# m4_Dev_Board.net
KiCad netlist of a schematic drawn in EAGLE
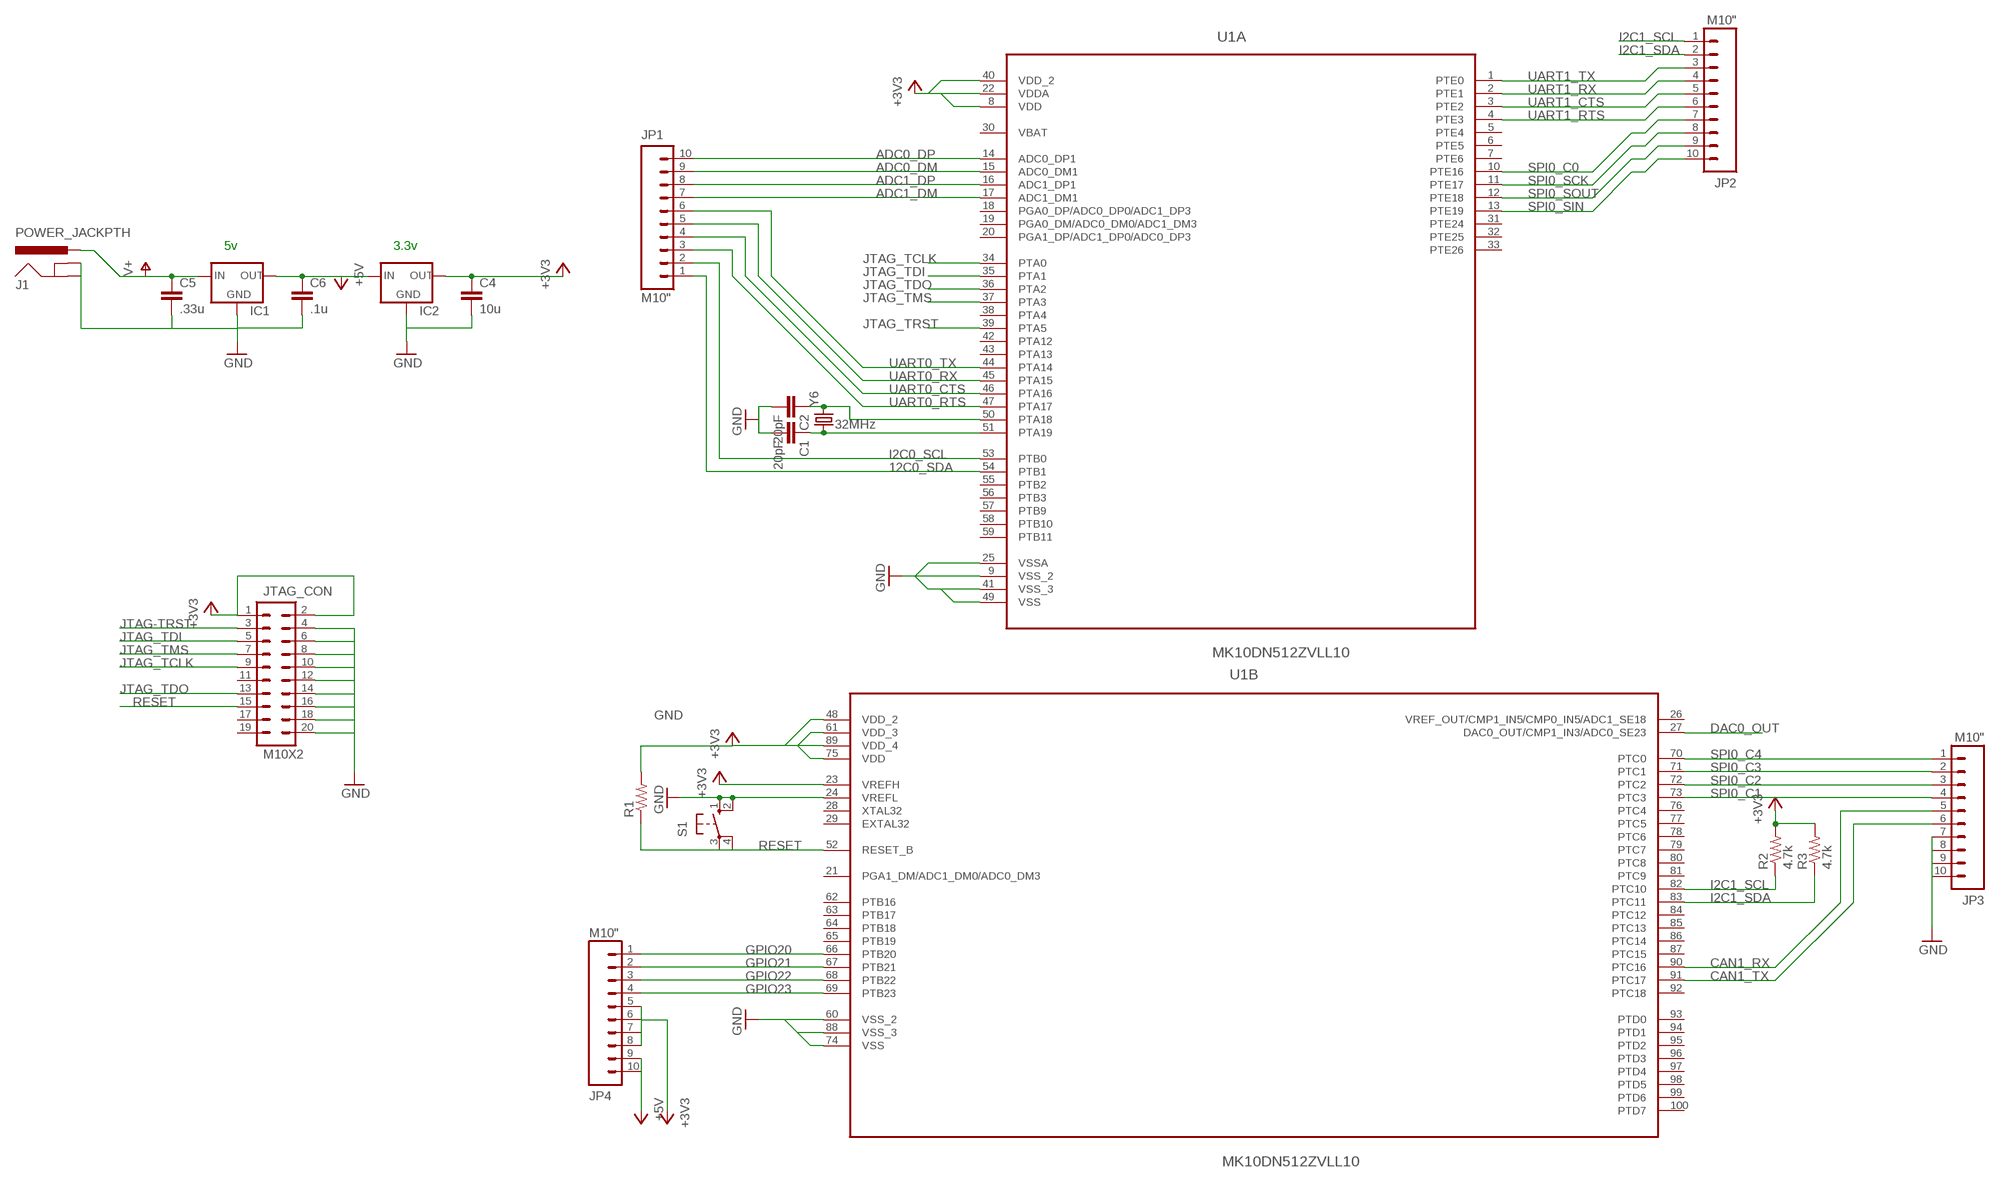
[diagram p0: schematic, sheet 1]

(export (version "E")
  (design (tool "Eeschema 10.0.6"))
  (components
    (comp (ref "C1")
      (value "20pF")
      (footprint "eagle-import:CAP-PTH-5MM")
      (libsource (lib "eagle-import") (part "CAPPTH1"))
    )
    (comp (ref "C2")
      (value "20pF")
      (footprint "eagle-import:CAP-PTH-5MM")
      (libsource (lib "eagle-import") (part "CAPPTH1"))
    )
    (comp (ref "C4")
      (value "10u")
      (footprint "eagle-import:CAP-PTH-5MM")
      (libsource (lib "eagle-import") (part "CAPPTH1"))
    )
    (comp (ref "C5")
      (value ".33u")
      (footprint "eagle-import:CAP-PTH-5MM")
      (libsource (lib "eagle-import") (part "CAPPTH1"))
    )
    (comp (ref "C6")
      (value ".1u")
      (footprint "eagle-import:CAP-PTH-5MM")
      (libsource (lib "eagle-import") (part "CAPPTH1"))
    )
    (comp (ref "IC1")
      (value "V_REG_78XXSINK")
      (footprint "eagle-import:TO220-IGO")
      (libsource (lib "eagle-import") (part "V_REG_78XXSINK"))
    )
    (comp (ref "IC2")
      (value "V_REG_78XXSINK")
      (footprint "eagle-import:TO220-IGO")
      (libsource (lib "eagle-import") (part "V_REG_78XXSINK"))
    )
    (comp (ref "J1")
      (value "POWER_JACKPTH")
      (footprint "eagle-import:POWER_JACK_PTH")
      (libsource (lib "eagle-import") (part "POWER_JACKPTH"))
    )
    (comp (ref "JP1")
      (value "M10\"")
      (footprint "eagle-import:1X10")
      (libsource (lib "eagle-import") (part "M10{dblquote}"))
    )
    (comp (ref "JP2")
      (value "M10\"")
      (footprint "eagle-import:1X10")
      (libsource (lib "eagle-import") (part "M10{dblquote}"))
    )
    (comp (ref "JP3")
      (value "M10\"")
      (footprint "eagle-import:1X10")
      (libsource (lib "eagle-import") (part "M10{dblquote}"))
    )
    (comp (ref "JP4")
      (value "M10\"")
      (footprint "eagle-import:1X10")
      (libsource (lib "eagle-import") (part "M10{dblquote}"))
    )
    (comp (ref "JTAG_CON")
      (value "M10X2")
      (footprint "eagle-import:2X10")
      (libsource (lib "eagle-import") (part "M10X2"))
    )
    (comp (ref "R1")
      (value "RESISTORPTH-1/4W")
      (footprint "eagle-import:AXIAL-0.4")
      (libsource (lib "eagle-import") (part "RESISTORPTH-1/4W"))
    )
    (comp (ref "R2")
      (value "4.7k")
      (footprint "eagle-import:AXIAL-0.4")
      (libsource (lib "eagle-import") (part "RESISTORPTH-1/4W"))
    )
    (comp (ref "R3")
      (value "4.7k")
      (footprint "eagle-import:AXIAL-0.4")
      (libsource (lib "eagle-import") (part "RESISTORPTH-1/4W"))
    )
    (comp (ref "S1")
      (value "10-XX")
      (footprint "eagle-import:B3F-10XX")
      (fields (field (name "MPN") "B3F-1000"))
      (libsource (lib "eagle-import") (part "10-XX"))
    )
    (comp (ref "U1")
      (value "MK10DN512ZVLL10")
      (footprint "eagle-import:QFP50P1600X1600X170-100N")
      (libsource (lib "eagle-import") (part "MK10DN512ZVLL10"))
    )
    (comp (ref "Y6")
      (value "32MHz")
      (footprint "eagle-import:CRYSTAL-SMD-5X3")
      (libsource (lib "eagle-import") (part "CRYSTAL5X3"))
    )
  )
  (nets
    (net (code "1") (name "+3V3") (class "Default")
      (node (ref "C4") (pin "1") (pinfunction "1_1") (pintype "passive"))
      (node (ref "IC2") (pin "OUT") (pinfunction "OUT_OUT") (pintype "output"))
      (node (ref "JP4") (pin "5") (pinfunction "5_5") (pintype "passive"))
      (node (ref "JP4") (pin "6") (pinfunction "6_6") (pintype "passive"))
      (node (ref "JP4") (pin "7") (pinfunction "7_7") (pintype "passive"))
      (node (ref "JP4") (pin "8") (pinfunction "8_8") (pintype "passive"))
      (node (ref "JTAG_CON") (pin "1") (pinfunction "1_1") (pintype "passive"))
      (node (ref "JTAG_CON") (pin "2") (pinfunction "2_2") (pintype "passive"))
      (node (ref "R1") (pin "P$2") (pinfunction "2_P$2") (pintype "passive"))
      (node (ref "R2") (pin "P$2") (pinfunction "2_P$2") (pintype "passive"))
      (node (ref "R3") (pin "P$2") (pinfunction "2_P$2") (pintype "passive"))
      (node (ref "U1") (pin "22") (pinfunction "VDDA_22") (pintype "power_in"))
      (node (ref "U1") (pin "23") (pinfunction "VREFH_23") (pintype "passive"))
      (node (ref "U1") (pin "40") (pinfunction "VDD_2_40") (pintype "power_in"))
      (node (ref "U1") (pin "48") (pinfunction "VDD_2_48") (pintype "power_in"))
      (node (ref "U1") (pin "61") (pinfunction "VDD_3_61") (pintype "power_in"))
      (node (ref "U1") (pin "75") (pinfunction "VDD_75") (pintype "power_in"))
      (node (ref "U1") (pin "8") (pinfunction "VDD_8") (pintype "power_in"))
      (node (ref "U1") (pin "89") (pinfunction "VDD_4_89") (pintype "power_in"))
    )
    (net (code "2") (name "+5V") (class "Default")
      (node (ref "C6") (pin "1") (pinfunction "1_1") (pintype "passive"))
      (node (ref "IC1") (pin "OUT") (pinfunction "OUT_OUT") (pintype "output"))
      (node (ref "IC2") (pin "IN") (pinfunction "IN_IN") (pintype "input"))
      (node (ref "JP4") (pin "10") (pinfunction "10_10") (pintype "passive"))
      (node (ref "JP4") (pin "9") (pinfunction "9_9") (pintype "passive"))
    )
    (net (code "3") (name "/12C0_SDA") (class "Default")
      (node (ref "JP1") (pin "1") (pinfunction "1_1") (pintype "passive"))
      (node (ref "U1") (pin "54") (pinfunction "PTB1_54") (pintype "bidirectional"))
    )
    (net (code "4") (name "/ADC0_DM") (class "Default")
      (node (ref "JP1") (pin "9") (pinfunction "9_9") (pintype "passive"))
      (node (ref "U1") (pin "15") (pinfunction "ADC0_DM1_15") (pintype "passive"))
    )
    (net (code "5") (name "/ADC0_DP") (class "Default")
      (node (ref "JP1") (pin "10") (pinfunction "10_10") (pintype "passive"))
      (node (ref "U1") (pin "14") (pinfunction "ADC0_DP1_14") (pintype "passive"))
    )
    (net (code "6") (name "/ADC1_DM") (class "Default")
      (node (ref "JP1") (pin "7") (pinfunction "7_7") (pintype "passive"))
      (node (ref "U1") (pin "17") (pinfunction "ADC1_DM1_17") (pintype "passive"))
    )
    (net (code "7") (name "/ADC1_DP") (class "Default")
      (node (ref "JP1") (pin "8") (pinfunction "8_8") (pintype "passive"))
      (node (ref "U1") (pin "16") (pinfunction "ADC1_DP1_16") (pintype "passive"))
    )
    (net (code "8") (name "/CAN1_RX") (class "Default")
      (node (ref "JP3") (pin "5") (pinfunction "5_5") (pintype "passive"))
      (node (ref "U1") (pin "90") (pinfunction "PTC16_90") (pintype "bidirectional"))
    )
    (net (code "9") (name "/CAN1_TX") (class "Default")
      (node (ref "JP3") (pin "6") (pinfunction "6_6") (pintype "passive"))
      (node (ref "U1") (pin "91") (pinfunction "PTC17_91") (pintype "bidirectional"))
    )
    (net (code "10") (name "/DAC0_OUT") (class "Default")
      (node (ref "U1") (pin "27") (pinfunction "DAC0_OUT/CMP1_IN3/ADC0_SE23_27") (pintype "passive"))
    )
    (net (code "11") (name "/GPIO20") (class "Default")
      (node (ref "JP4") (pin "1") (pinfunction "1_1") (pintype "passive"))
      (node (ref "U1") (pin "66") (pinfunction "PTB20_66") (pintype "bidirectional"))
    )
    (net (code "12") (name "/GPIO21") (class "Default")
      (node (ref "JP4") (pin "2") (pinfunction "2_2") (pintype "passive"))
      (node (ref "U1") (pin "67") (pinfunction "PTB21_67") (pintype "bidirectional"))
    )
    (net (code "13") (name "/GPIO22") (class "Default")
      (node (ref "JP4") (pin "3") (pinfunction "3_3") (pintype "passive"))
      (node (ref "U1") (pin "68") (pinfunction "PTB22_68") (pintype "bidirectional"))
    )
    (net (code "14") (name "/GPIO23") (class "Default")
      (node (ref "JP4") (pin "4") (pinfunction "4_4") (pintype "passive"))
      (node (ref "U1") (pin "69") (pinfunction "PTB23_69") (pintype "bidirectional"))
    )
    (net (code "15") (name "/I2C0_SCL") (class "Default")
      (node (ref "JP1") (pin "2") (pinfunction "2_2") (pintype "passive"))
      (node (ref "U1") (pin "53") (pinfunction "PTB0_53") (pintype "bidirectional"))
    )
    (net (code "16") (name "/I2C1_SCL") (class "Default")
      (node (ref "JP2") (pin "1") (pinfunction "1_1") (pintype "passive"))
      (node (ref "R2") (pin "P$1") (pinfunction "1_P$1") (pintype "passive"))
      (node (ref "U1") (pin "82") (pinfunction "PTC10_82") (pintype "bidirectional"))
    )
    (net (code "17") (name "/I2C1_SDA") (class "Default")
      (node (ref "JP2") (pin "2") (pinfunction "2_2") (pintype "passive"))
      (node (ref "R3") (pin "P$1") (pinfunction "1_P$1") (pintype "passive"))
      (node (ref "U1") (pin "83") (pinfunction "PTC11_83") (pintype "bidirectional"))
    )
    (net (code "18") (name "/JTAG-TRST") (class "Default")
      (node (ref "JTAG_CON") (pin "3") (pinfunction "3_3") (pintype "passive"))
    )
    (net (code "19") (name "/JTAG_TCLK") (class "Default")
      (node (ref "JTAG_CON") (pin "9") (pinfunction "9_9") (pintype "passive"))
      (node (ref "U1") (pin "34") (pinfunction "PTA0_34") (pintype "bidirectional"))
    )
    (net (code "20") (name "/JTAG_TDI") (class "Default")
      (node (ref "JTAG_CON") (pin "5") (pinfunction "5_5") (pintype "passive"))
      (node (ref "U1") (pin "35") (pinfunction "PTA1_35") (pintype "bidirectional"))
    )
    (net (code "21") (name "/JTAG_TDO") (class "Default")
      (node (ref "JTAG_CON") (pin "13") (pinfunction "13_13") (pintype "passive"))
      (node (ref "U1") (pin "36") (pinfunction "PTA2_36") (pintype "bidirectional"))
    )
    (net (code "22") (name "/JTAG_TMS") (class "Default")
      (node (ref "JTAG_CON") (pin "7") (pinfunction "7_7") (pintype "passive"))
      (node (ref "U1") (pin "37") (pinfunction "PTA3_37") (pintype "bidirectional"))
    )
    (net (code "23") (name "/JTAG_TRST") (class "Default")
      (node (ref "U1") (pin "39") (pinfunction "PTA5_39") (pintype "bidirectional"))
    )
    (net (code "24") (name "/RESET") (class "Default")
      (node (ref "JTAG_CON") (pin "15") (pinfunction "15_15") (pintype "passive"))
      (node (ref "R1") (pin "P$1") (pinfunction "1_P$1") (pintype "passive"))
      (node (ref "S1") (pin "3") (pinfunction "P_3") (pintype "passive"))
      (node (ref "S1") (pin "4") (pinfunction "P1_4") (pintype "passive"))
      (node (ref "U1") (pin "52") (pinfunction "RESET_B_52") (pintype "passive"))
    )
    (net (code "25") (name "/SPI0_C0") (class "Default")
      (node (ref "JP2") (pin "7") (pinfunction "7_7") (pintype "passive"))
      (node (ref "U1") (pin "10") (pinfunction "PTE16_10") (pintype "bidirectional"))
    )
    (net (code "26") (name "/SPI0_C1") (class "Default")
      (node (ref "JP3") (pin "4") (pinfunction "4_4") (pintype "passive"))
      (node (ref "U1") (pin "73") (pinfunction "PTC3_73") (pintype "bidirectional"))
    )
    (net (code "27") (name "/SPI0_C2") (class "Default")
      (node (ref "JP3") (pin "3") (pinfunction "3_3") (pintype "passive"))
      (node (ref "U1") (pin "72") (pinfunction "PTC2_72") (pintype "bidirectional"))
    )
    (net (code "28") (name "/SPI0_C3") (class "Default")
      (node (ref "JP3") (pin "2") (pinfunction "2_2") (pintype "passive"))
      (node (ref "U1") (pin "71") (pinfunction "PTC1_71") (pintype "bidirectional"))
    )
    (net (code "29") (name "/SPI0_C4") (class "Default")
      (node (ref "JP3") (pin "1") (pinfunction "1_1") (pintype "passive"))
      (node (ref "U1") (pin "70") (pinfunction "PTC0_70") (pintype "bidirectional"))
    )
    (net (code "30") (name "/SPI0_SCK") (class "Default")
      (node (ref "JP2") (pin "8") (pinfunction "8_8") (pintype "passive"))
      (node (ref "U1") (pin "11") (pinfunction "PTE17_11") (pintype "bidirectional"))
    )
    (net (code "31") (name "/SPI0_SIN") (class "Default")
      (node (ref "JP2") (pin "10") (pinfunction "10_10") (pintype "passive"))
      (node (ref "U1") (pin "13") (pinfunction "PTE19_13") (pintype "bidirectional"))
    )
    (net (code "32") (name "/SPI0_SOUT") (class "Default")
      (node (ref "JP2") (pin "9") (pinfunction "9_9") (pintype "passive"))
      (node (ref "U1") (pin "12") (pinfunction "PTE18_12") (pintype "bidirectional"))
    )
    (net (code "33") (name "/UART0_CTS") (class "Default")
      (node (ref "JP1") (pin "4") (pinfunction "4_4") (pintype "passive"))
      (node (ref "U1") (pin "46") (pinfunction "PTA16_46") (pintype "bidirectional"))
    )
    (net (code "34") (name "/UART0_RTS") (class "Default")
      (node (ref "JP1") (pin "3") (pinfunction "3_3") (pintype "passive"))
      (node (ref "U1") (pin "47") (pinfunction "PTA17_47") (pintype "bidirectional"))
    )
    (net (code "35") (name "/UART0_RX") (class "Default")
      (node (ref "JP1") (pin "5") (pinfunction "5_5") (pintype "passive"))
      (node (ref "U1") (pin "45") (pinfunction "PTA15_45") (pintype "bidirectional"))
    )
    (net (code "36") (name "/UART0_TX") (class "Default")
      (node (ref "JP1") (pin "6") (pinfunction "6_6") (pintype "passive"))
      (node (ref "U1") (pin "44") (pinfunction "PTA14_44") (pintype "bidirectional"))
    )
    (net (code "37") (name "/UART1_CTS") (class "Default")
      (node (ref "JP2") (pin "5") (pinfunction "5_5") (pintype "passive"))
      (node (ref "U1") (pin "3") (pinfunction "PTE2_3") (pintype "bidirectional"))
    )
    (net (code "38") (name "/UART1_RTS") (class "Default")
      (node (ref "JP2") (pin "6") (pinfunction "6_6") (pintype "passive"))
      (node (ref "U1") (pin "4") (pinfunction "PTE3_4") (pintype "bidirectional"))
    )
    (net (code "39") (name "/UART1_RX") (class "Default")
      (node (ref "JP2") (pin "4") (pinfunction "4_4") (pintype "passive"))
      (node (ref "U1") (pin "2") (pinfunction "PTE1_2") (pintype "bidirectional"))
    )
    (net (code "40") (name "/UART1_TX") (class "Default")
      (node (ref "JP2") (pin "3") (pinfunction "3_3") (pintype "passive"))
      (node (ref "U1") (pin "1") (pinfunction "PTE0_1") (pintype "bidirectional"))
    )
    (net (code "41") (name "/VBAT") (class "Default")
      (node (ref "U1") (pin "30") (pinfunction "VBAT_30") (pintype "power_in"))
    )
    (net (code "42") (name "GND") (class "Default")
      (node (ref "C1") (pin "2") (pinfunction "2_2") (pintype "passive"))
      (node (ref "C2") (pin "2") (pinfunction "2_2") (pintype "passive"))
      (node (ref "C4") (pin "2") (pinfunction "2_2") (pintype "passive"))
      (node (ref "C5") (pin "2") (pinfunction "2_2") (pintype "passive"))
      (node (ref "C6") (pin "2") (pinfunction "2_2") (pintype "passive"))
      (node (ref "IC1") (pin "GND") (pinfunction "GND_GND") (pintype "input"))
      (node (ref "IC2") (pin "GND") (pinfunction "GND_GND") (pintype "input"))
      (node (ref "J1") (pin "GND") (pinfunction "GND_GND") (pintype "bidirectional"))
      (node (ref "J1") (pin "GNDBREAK") (pinfunction "GNDBREAK_GNDBREAK") (pintype "bidirectional"))
      (node (ref "JP3") (pin "10") (pinfunction "10_10") (pintype "passive"))
      (node (ref "JP3") (pin "7") (pinfunction "7_7") (pintype "passive"))
      (node (ref "JP3") (pin "8") (pinfunction "8_8") (pintype "passive"))
      (node (ref "JP3") (pin "9") (pinfunction "9_9") (pintype "passive"))
      (node (ref "JTAG_CON") (pin "10") (pinfunction "10_10") (pintype "passive"))
      (node (ref "JTAG_CON") (pin "12") (pinfunction "12_12") (pintype "passive"))
      (node (ref "JTAG_CON") (pin "14") (pinfunction "14_14") (pintype "passive"))
      (node (ref "JTAG_CON") (pin "16") (pinfunction "16_16") (pintype "passive"))
      (node (ref "JTAG_CON") (pin "18") (pinfunction "18_18") (pintype "passive"))
      (node (ref "JTAG_CON") (pin "20") (pinfunction "20_20") (pintype "passive"))
      (node (ref "JTAG_CON") (pin "4") (pinfunction "4_4") (pintype "passive"))
      (node (ref "JTAG_CON") (pin "6") (pinfunction "6_6") (pintype "passive"))
      (node (ref "JTAG_CON") (pin "8") (pinfunction "8_8") (pintype "passive"))
      (node (ref "S1") (pin "1") (pinfunction "S_1") (pintype "passive"))
      (node (ref "S1") (pin "2") (pinfunction "S1_2") (pintype "passive"))
      (node (ref "U1") (pin "24") (pinfunction "VREFL_24") (pintype "passive"))
      (node (ref "U1") (pin "25") (pinfunction "VSSA_25") (pintype "passive"))
      (node (ref "U1") (pin "41") (pinfunction "VSS_3_41") (pintype "passive"))
      (node (ref "U1") (pin "49") (pinfunction "VSS_49") (pintype "passive"))
      (node (ref "U1") (pin "60") (pinfunction "VSS_2_60") (pintype "passive"))
      (node (ref "U1") (pin "74") (pinfunction "VSS_74") (pintype "passive"))
      (node (ref "U1") (pin "88") (pinfunction "VSS_3_88") (pintype "passive"))
      (node (ref "U1") (pin "9") (pinfunction "VSS_2_9") (pintype "passive"))
    )
    (net (code "43") (name "Net-(U1A-PTA18)") (class "Default")
      (node (ref "C2") (pin "1") (pinfunction "1_1") (pintype "passive"))
      (node (ref "U1") (pin "50") (pinfunction "PTA18_50") (pintype "bidirectional"))
      (node (ref "Y6") (pin "3") (pinfunction "2_3") (pintype "passive"))
    )
    (net (code "44") (name "Net-(U1A-PTA19)") (class "Default")
      (node (ref "C1") (pin "1") (pinfunction "1_1") (pintype "passive"))
      (node (ref "U1") (pin "51") (pinfunction "PTA19_51") (pintype "bidirectional"))
      (node (ref "Y6") (pin "1") (pinfunction "1_1") (pintype "passive"))
    )
    (net (code "45") (name "V+") (class "Default")
      (node (ref "C5") (pin "1") (pinfunction "1_1") (pintype "passive"))
      (node (ref "IC1") (pin "IN") (pinfunction "IN_IN") (pintype "input"))
      (node (ref "J1") (pin "PWR") (pinfunction "PWR_PWR") (pintype "bidirectional"))
    )
    (net (code "46") (name "unconnected-(JTAG_CON-Pad11)") (class "Default")
      (node (ref "JTAG_CON") (pin "11") (pinfunction "11_11") (pintype "passive"))
    )
    (net (code "47") (name "unconnected-(JTAG_CON-Pad17)") (class "Default")
      (node (ref "JTAG_CON") (pin "17") (pinfunction "17_17") (pintype "passive"))
    )
    (net (code "48") (name "unconnected-(JTAG_CON-Pad19)") (class "Default")
      (node (ref "JTAG_CON") (pin "19") (pinfunction "19_19") (pintype "passive"))
    )
    (net (code "49") (name "unconnected-(U1A-PGA0_DM{slash}ADC0_DM0{slash}ADC1_DM3-Pad19)") (class "Default")
      (node (ref "U1") (pin "19") (pinfunction "PGA0_DM/ADC0_DM0/ADC1_DM3_19") (pintype "passive"))
    )
    (net (code "50") (name "unconnected-(U1A-PGA0_DP{slash}ADC0_DP0{slash}ADC1_DP3-Pad18)") (class "Default")
      (node (ref "U1") (pin "18") (pinfunction "PGA0_DP/ADC0_DP0/ADC1_DP3_18") (pintype "passive"))
    )
    (net (code "51") (name "unconnected-(U1A-PGA1_DP{slash}ADC1_DP0{slash}ADC0_DP3-Pad20)") (class "Default")
      (node (ref "U1") (pin "20") (pinfunction "PGA1_DP/ADC1_DP0/ADC0_DP3_20") (pintype "passive"))
    )
    (net (code "52") (name "unconnected-(U1A-PTA4-Pad38)") (class "Default")
      (node (ref "U1") (pin "38") (pinfunction "PTA4_38") (pintype "bidirectional"))
    )
    (net (code "53") (name "unconnected-(U1A-PTA12-Pad42)") (class "Default")
      (node (ref "U1") (pin "42") (pinfunction "PTA12_42") (pintype "bidirectional"))
    )
    (net (code "54") (name "unconnected-(U1A-PTA13-Pad43)") (class "Default")
      (node (ref "U1") (pin "43") (pinfunction "PTA13_43") (pintype "bidirectional"))
    )
    (net (code "55") (name "unconnected-(U1A-PTB2-Pad55)") (class "Default")
      (node (ref "U1") (pin "55") (pinfunction "PTB2_55") (pintype "bidirectional"))
    )
    (net (code "56") (name "unconnected-(U1A-PTB3-Pad56)") (class "Default")
      (node (ref "U1") (pin "56") (pinfunction "PTB3_56") (pintype "bidirectional"))
    )
    (net (code "57") (name "unconnected-(U1A-PTB9-Pad57)") (class "Default")
      (node (ref "U1") (pin "57") (pinfunction "PTB9_57") (pintype "bidirectional"))
    )
    (net (code "58") (name "unconnected-(U1A-PTB10-Pad58)") (class "Default")
      (node (ref "U1") (pin "58") (pinfunction "PTB10_58") (pintype "bidirectional"))
    )
    (net (code "59") (name "unconnected-(U1A-PTB11-Pad59)") (class "Default")
      (node (ref "U1") (pin "59") (pinfunction "PTB11_59") (pintype "bidirectional"))
    )
    (net (code "60") (name "unconnected-(U1A-PTE4-Pad5)") (class "Default")
      (node (ref "U1") (pin "5") (pinfunction "PTE4_5") (pintype "bidirectional"))
    )
    (net (code "61") (name "unconnected-(U1A-PTE5-Pad6)") (class "Default")
      (node (ref "U1") (pin "6") (pinfunction "PTE5_6") (pintype "bidirectional"))
    )
    (net (code "62") (name "unconnected-(U1A-PTE6-Pad7)") (class "Default")
      (node (ref "U1") (pin "7") (pinfunction "PTE6_7") (pintype "bidirectional"))
    )
    (net (code "63") (name "unconnected-(U1A-PTE24-Pad31)") (class "Default")
      (node (ref "U1") (pin "31") (pinfunction "PTE24_31") (pintype "bidirectional"))
    )
    (net (code "64") (name "unconnected-(U1A-PTE25-Pad32)") (class "Default")
      (node (ref "U1") (pin "32") (pinfunction "PTE25_32") (pintype "bidirectional"))
    )
    (net (code "65") (name "unconnected-(U1A-PTE26-Pad33)") (class "Default")
      (node (ref "U1") (pin "33") (pinfunction "PTE26_33") (pintype "bidirectional"))
    )
    (net (code "66") (name "unconnected-(U1B-EXTAL32-Pad29)") (class "Default")
      (node (ref "U1") (pin "29") (pinfunction "EXTAL32_29") (pintype "passive"))
    )
    (net (code "67") (name "unconnected-(U1B-PGA1_DM{slash}ADC1_DM0{slash}ADC0_DM3-Pad21)") (class "Default")
      (node (ref "U1") (pin "21") (pinfunction "PGA1_DM/ADC1_DM0/ADC0_DM3_21") (pintype "passive"))
    )
    (net (code "68") (name "unconnected-(U1B-PTB16-Pad62)") (class "Default")
      (node (ref "U1") (pin "62") (pinfunction "PTB16_62") (pintype "bidirectional"))
    )
    (net (code "69") (name "unconnected-(U1B-PTB17-Pad63)") (class "Default")
      (node (ref "U1") (pin "63") (pinfunction "PTB17_63") (pintype "bidirectional"))
    )
    (net (code "70") (name "unconnected-(U1B-PTB18-Pad64)") (class "Default")
      (node (ref "U1") (pin "64") (pinfunction "PTB18_64") (pintype "bidirectional"))
    )
    (net (code "71") (name "unconnected-(U1B-PTB19-Pad65)") (class "Default")
      (node (ref "U1") (pin "65") (pinfunction "PTB19_65") (pintype "bidirectional"))
    )
    (net (code "72") (name "unconnected-(U1B-PTC4-Pad76)") (class "Default")
      (node (ref "U1") (pin "76") (pinfunction "PTC4_76") (pintype "bidirectional"))
    )
    (net (code "73") (name "unconnected-(U1B-PTC5-Pad77)") (class "Default")
      (node (ref "U1") (pin "77") (pinfunction "PTC5_77") (pintype "bidirectional"))
    )
    (net (code "74") (name "unconnected-(U1B-PTC6-Pad78)") (class "Default")
      (node (ref "U1") (pin "78") (pinfunction "PTC6_78") (pintype "bidirectional"))
    )
    (net (code "75") (name "unconnected-(U1B-PTC7-Pad79)") (class "Default")
      (node (ref "U1") (pin "79") (pinfunction "PTC7_79") (pintype "bidirectional"))
    )
    (net (code "76") (name "unconnected-(U1B-PTC8-Pad80)") (class "Default")
      (node (ref "U1") (pin "80") (pinfunction "PTC8_80") (pintype "bidirectional"))
    )
    (net (code "77") (name "unconnected-(U1B-PTC9-Pad81)") (class "Default")
      (node (ref "U1") (pin "81") (pinfunction "PTC9_81") (pintype "bidirectional"))
    )
    (net (code "78") (name "unconnected-(U1B-PTC12-Pad84)") (class "Default")
      (node (ref "U1") (pin "84") (pinfunction "PTC12_84") (pintype "bidirectional"))
    )
    (net (code "79") (name "unconnected-(U1B-PTC13-Pad85)") (class "Default")
      (node (ref "U1") (pin "85") (pinfunction "PTC13_85") (pintype "bidirectional"))
    )
    (net (code "80") (name "unconnected-(U1B-PTC14-Pad86)") (class "Default")
      (node (ref "U1") (pin "86") (pinfunction "PTC14_86") (pintype "bidirectional"))
    )
    (net (code "81") (name "unconnected-(U1B-PTC15-Pad87)") (class "Default")
      (node (ref "U1") (pin "87") (pinfunction "PTC15_87") (pintype "bidirectional"))
    )
    (net (code "82") (name "unconnected-(U1B-PTC18-Pad92)") (class "Default")
      (node (ref "U1") (pin "92") (pinfunction "PTC18_92") (pintype "bidirectional"))
    )
    (net (code "83") (name "unconnected-(U1B-PTD0-Pad93)") (class "Default")
      (node (ref "U1") (pin "93") (pinfunction "PTD0_93") (pintype "bidirectional"))
    )
    (net (code "84") (name "unconnected-(U1B-PTD1-Pad94)") (class "Default")
      (node (ref "U1") (pin "94") (pinfunction "PTD1_94") (pintype "bidirectional"))
    )
    (net (code "85") (name "unconnected-(U1B-PTD2-Pad95)") (class "Default")
      (node (ref "U1") (pin "95") (pinfunction "PTD2_95") (pintype "bidirectional"))
    )
    (net (code "86") (name "unconnected-(U1B-PTD3-Pad96)") (class "Default")
      (node (ref "U1") (pin "96") (pinfunction "PTD3_96") (pintype "bidirectional"))
    )
    (net (code "87") (name "unconnected-(U1B-PTD4-Pad97)") (class "Default")
      (node (ref "U1") (pin "97") (pinfunction "PTD4_97") (pintype "bidirectional"))
    )
    (net (code "88") (name "unconnected-(U1B-PTD5-Pad98)") (class "Default")
      (node (ref "U1") (pin "98") (pinfunction "PTD5_98") (pintype "bidirectional"))
    )
    (net (code "89") (name "unconnected-(U1B-PTD6-Pad99)") (class "Default")
      (node (ref "U1") (pin "99") (pinfunction "PTD6_99") (pintype "bidirectional"))
    )
    (net (code "90") (name "unconnected-(U1B-PTD7-Pad100)") (class "Default")
      (node (ref "U1") (pin "100") (pinfunction "PTD7_100") (pintype "bidirectional"))
    )
    (net (code "91") (name "unconnected-(U1B-VREF_OUT{slash}CMP1_IN5{slash}CMP0_IN5{slash}ADC1_SE18-Pad26)") (class "Default")
      (node (ref "U1") (pin "26") (pinfunction "VREF_OUT/CMP1_IN5/CMP0_IN5/ADC1_SE18_26") (pintype "passive"))
    )
    (net (code "92") (name "unconnected-(U1B-XTAL32-Pad28)") (class "Default")
      (node (ref "U1") (pin "28") (pinfunction "XTAL32_28") (pintype "passive"))
    )
  )
)
